# Shundown_Mechanism.net
KiCad netlist of a schematic drawn in Altium Designer
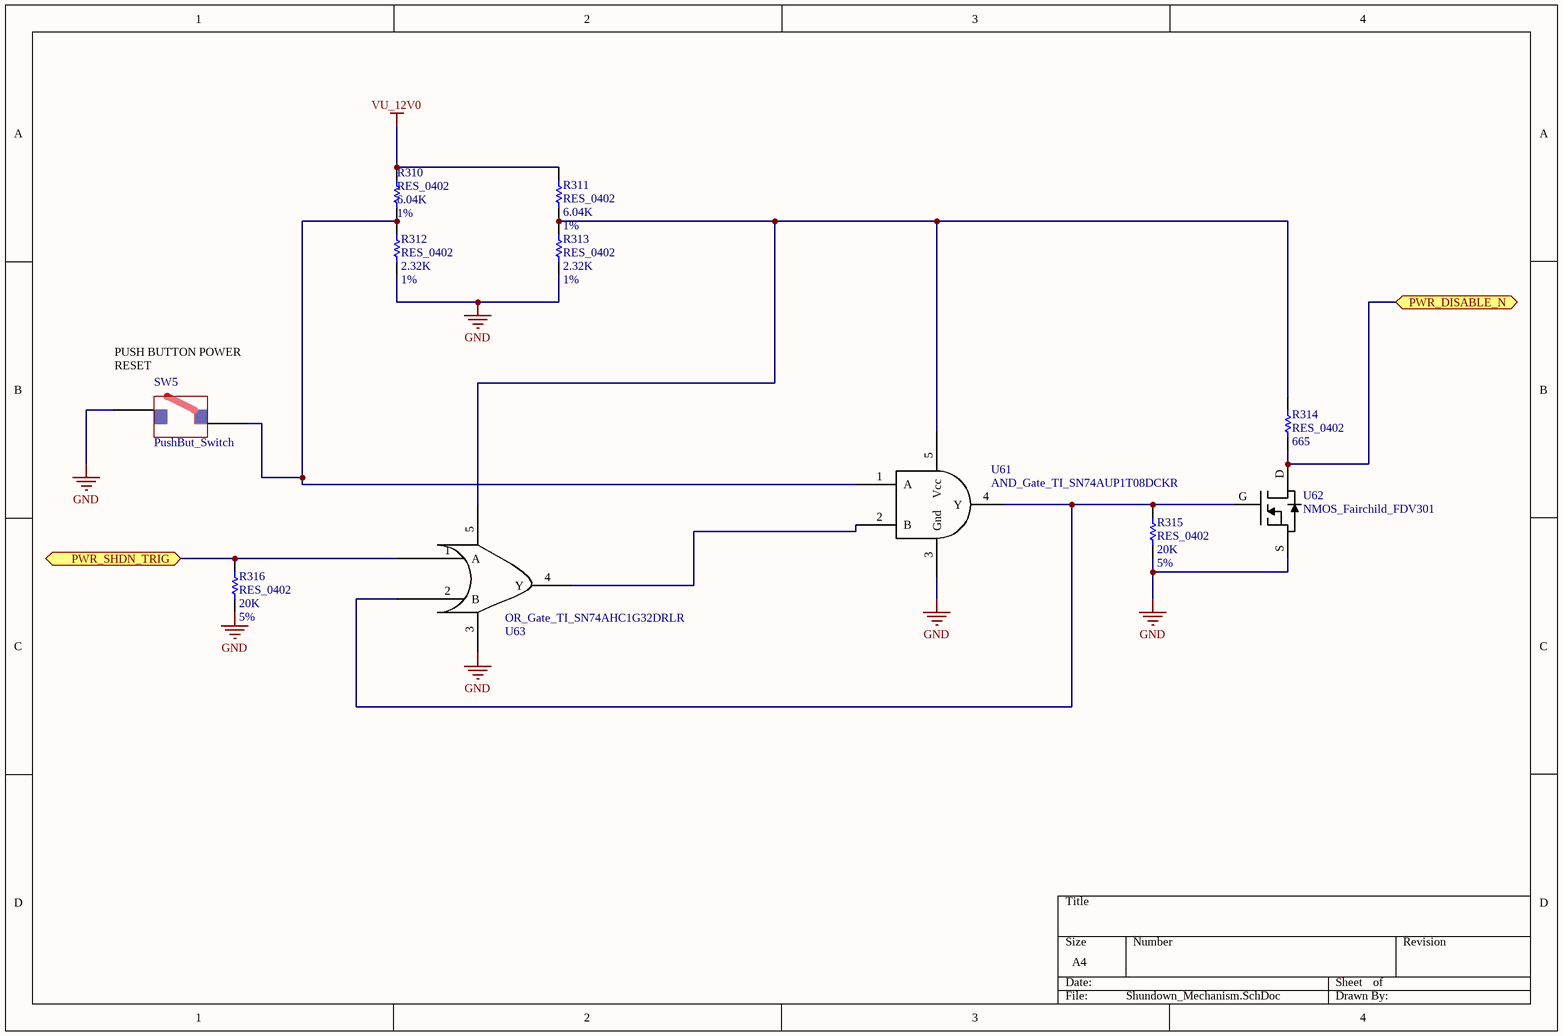
[diagram p0: Shundown_Mechanism.SchDoc]

(export (version "E")
  (design (tool "Eeschema 10.0.6"))
  (components
    (comp (ref "R310")
      (value "RES_0402")
      (footprint "RESC0402(1005)_N")
      (description "RES 6.04K OHM 1/10W 1% 0402 SMD")
      (fields
        (field (name "ALTIUM_VALUE") "6.04K")
        (field (name "TOLERANCE") "1%")
        (field (name "PART NUMBER") "ERJ-2RKF6041X")
        (field (name "MANUFACTURER") "Panasonic Electronic Components")
      )
      (libsource (lib "COMRAD_Database") (part "RES_0402"))
    )
    (comp (ref "R311")
      (value "RES_0402")
      (footprint "RESC0402(1005)_N")
      (description "RES 6.04K OHM 1/10W 1% 0402 SMD")
      (fields
        (field (name "ALTIUM_VALUE") "6.04K")
        (field (name "TOLERANCE") "1%")
        (field (name "PART NUMBER") "ERJ-2RKF6041X")
        (field (name "MANUFACTURER") "Panasonic Electronic Components")
      )
      (libsource (lib "COMRAD_Database") (part "RES_0402"))
    )
    (comp (ref "R312")
      (value "RES_0402")
      (footprint "RESC0402(1005)_N")
      (description "2.32K ohm, 1% 1/16W, 0402")
      (fields
        (field (name "ALTIUM_VALUE") "2.32K")
        (field (name "TOLERANCE") "1%")
        (field (name "PART NUMBER") "ERJ-2RKF2321X")
        (field (name "MANUFACTURER") "Panasonic - ECG")
      )
      (libsource (lib "COMRAD_Database") (part "RES_0402"))
    )
    (comp (ref "R313")
      (value "RES_0402")
      (footprint "RESC0402(1005)_N")
      (description "2.32K ohm, 1% 1/16W, 0402")
      (fields
        (field (name "ALTIUM_VALUE") "2.32K")
        (field (name "TOLERANCE") "1%")
        (field (name "PART NUMBER") "ERJ-2RKF2321X")
        (field (name "MANUFACTURER") "Panasonic - ECG")
      )
      (libsource (lib "COMRAD_Database") (part "RES_0402"))
    )
    (comp (ref "R314")
      (value "RES_0402")
      (footprint "RESC0402(1005)_N")
      (description "RES 665 OHM 1/10W 1% 0402 SMD")
      (fields
        (field (name "ALTIUM_VALUE") "665")
        (field (name "PART NUMBER") "ERJ-2RKF6650X")
        (field (name "MANUFACTURER") "Panasonic Electronic Components")
      )
      (libsource (lib "COMRAD_Database") (part "RES_0402"))
    )
    (comp (ref "R315")
      (value "RES_0402")
      (footprint "RESC0402(1005)_N:RESC0402(1005)_N")
      (description "20K ohm, 5%, 1/16W, 0402")
      (fields
        (field (name "ALTIUM_VALUE") "20K")
        (field (name "TOLERANCE") "5%")
        (field (name "PART NUMBER") "ERJ-2GEJ203X")
        (field (name "MANUFACTURER") "Panasonic - ECG")
      )
      (libsource (lib "COMRAD_Database") (part "RES_0402"))
    )
    (comp (ref "R316")
      (value "RES_0402")
      (footprint "RESC0402(1005)_N:RESC0402(1005)_N")
      (description "20K ohm, 5%, 1/16W, 0402")
      (fields
        (field (name "ALTIUM_VALUE") "20K")
        (field (name "TOLERANCE") "5%")
        (field (name "PART NUMBER") "ERJ-2GEJ203X")
        (field (name "MANUFACTURER") "Panasonic - ECG")
      )
      (libsource (lib "COMRAD_Database") (part "RES_0402"))
    )
    (comp (ref "SW5")
      (value "PushBut_Switch")
      (footprint "PushButtonSwitch_CnK_1.14002.1110000")
      (description "SWITCH PUSH SPST-NO 0.1A 35V")
      (fields (field (name "PART NUMBER") "1.14002.1110000") (field (name "MANUFACTURER") "C&K Components"))
      (libsource (lib "COMRAD_Database") (part "PushBut_Switch"))
    )
    (comp (ref "U61")
      (value "AND_Gate_TI_SN74AUP1T08DCKR")
      (footprint "AND_Gate_TI_SN74AUP1T08DCKR_SC70-5")
      (description "IC GATE POS-AND SLG 2INP SC70-5")
      (fields
        (field (name "PART NUMBER") "SN74AUP1T08DCKR")
        (field (name "MANUFACTURER") "Texas Instruments")
      )
      (libsource (lib "COMRAD_Database") (part "AND_Gate_TI_SN74AUP1T08DCKR"))
    )
    (comp (ref "U62")
      (value "NMOS_Fairchild_FDV301")
      (footprint "NMOS_Fairchild_FDV301_SOT23-3")
      (description "MOSFET N-CH 25V 220MA SOT-23")
      (fields (field (name "PART NUMBER") "FDV301N") (field (name "MANUFACTURER") "Fairchild Semiconductor"))
      (libsource (lib "COMRAD_Database") (part "NMOS_Fairchild_FDV301"))
    )
    (comp (ref "U63")
      (value "OR_Gate_TI_SN74AHC1G32DRLR")
      (footprint "OR_Gate_TI_SN74AHC1G32DRLR_DRL-5")
      (description "IC SNGL 2-IN POS-OR GATE SOT-5")
      (fields
        (field (name "PART NUMBER") "SN74AHC1G32DRLR")
        (field (name "MANUFACTURER") "Texas Instruments")
      )
      (libsource (lib "COMRAD_Database") (part "OR_Gate_TI_SN74AHC1G32DRLR"))
    )
  )
  (nets
    (net (code "1") (name "/PWR_DISABLE_N") (class "Default")
      (node (ref "R314") (pin "1") (pinfunction "1_1") (pintype "passive"))
      (node (ref "U62") (pin "D") (pintype "passive"))
    )
    (net (code "2") (name "/PWR_SHDN_TRIG") (class "Default")
      (node (ref "R316") (pin "2") (pinfunction "2_2") (pintype "passive"))
      (node (ref "U63") (pin "1") (pinfunction "A_1") (pintype "passive"))
    )
    (net (code "3") (name "GND") (class "Default")
      (node (ref "R312") (pin "1") (pinfunction "1_1") (pintype "passive"))
      (node (ref "R313") (pin "1") (pinfunction "1_1") (pintype "passive"))
      (node (ref "R315") (pin "1") (pinfunction "1_1") (pintype "passive"))
      (node (ref "R316") (pin "1") (pinfunction "1_1") (pintype "passive"))
      (node (ref "SW5") (pin "3") (pintype "passive"))
      (node (ref "U61") (pin "3") (pinfunction "Gnd_3") (pintype "passive"))
      (node (ref "U62") (pin "S") (pintype "passive"))
      (node (ref "U63") (pin "3") (pintype "passive"))
    )
    (net (code "4") (name "Net-(U61-A)") (class "Default")
      (node (ref "R310") (pin "1") (pinfunction "1_1") (pintype "passive"))
      (node (ref "R312") (pin "2") (pinfunction "2_2") (pintype "passive"))
      (node (ref "SW5") (pin "4") (pintype "passive"))
      (node (ref "U61") (pin "1") (pinfunction "A_1") (pintype "passive"))
    )
    (net (code "5") (name "Net-(U61-B)") (class "Default")
      (node (ref "U61") (pin "2") (pinfunction "B_2") (pintype "passive"))
      (node (ref "U63") (pin "4") (pinfunction "Y_4") (pintype "passive"))
    )
    (net (code "6") (name "Net-(U61-Vcc)") (class "Default")
      (node (ref "R311") (pin "1") (pinfunction "1_1") (pintype "passive"))
      (node (ref "R313") (pin "2") (pinfunction "2_2") (pintype "passive"))
      (node (ref "R314") (pin "2") (pinfunction "2_2") (pintype "passive"))
      (node (ref "U61") (pin "5") (pinfunction "Vcc_5") (pintype "passive"))
      (node (ref "U63") (pin "5") (pintype "passive"))
    )
    (net (code "7") (name "Net-(U61-Y)") (class "Default")
      (node (ref "R315") (pin "2") (pinfunction "2_2") (pintype "passive"))
      (node (ref "U61") (pin "4") (pinfunction "Y_4") (pintype "passive"))
      (node (ref "U62") (pin "G") (pintype "passive"))
      (node (ref "U63") (pin "2") (pinfunction "B_2") (pintype "passive"))
    )
    (net (code "8") (name "VU_12V0") (class "Default")
      (node (ref "R310") (pin "2") (pinfunction "2_2") (pintype "passive"))
      (node (ref "R311") (pin "2") (pinfunction "2_2") (pintype "passive"))
    )
  )
)
